# Cautin.net
KiCad netlist of a schematic drawn in EAGLE
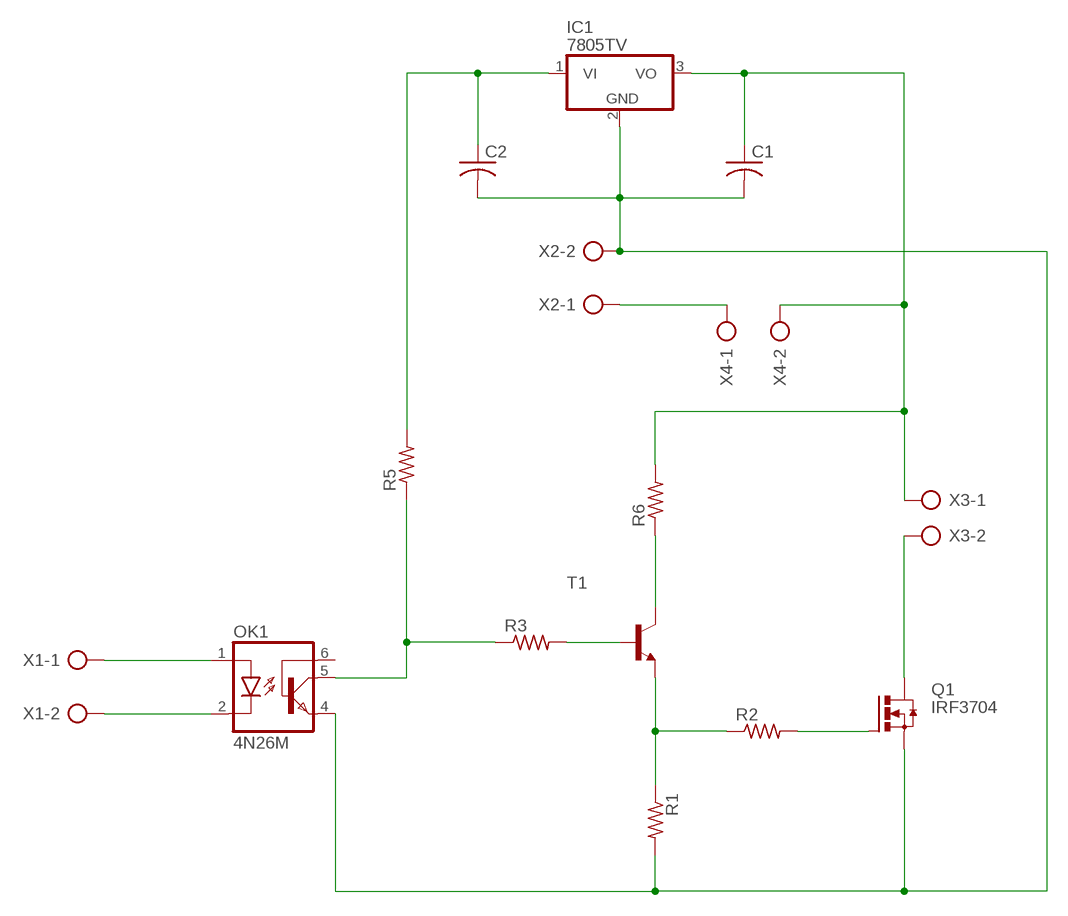
[diagram p0: schematic, sheet 1]

(export (version "E")
  (design (tool "Eeschema 10.0.6"))
  (components
    (comp (ref "C1")
      (value "C-US025-024X044")
      (footprint "eagle-import:C025-024X044")
      (libsource (lib "eagle-import") (part "C-US025-024X044"))
    )
    (comp (ref "C2")
      (value "C-US025-024X044")
      (footprint "eagle-import:C025-024X044")
      (libsource (lib "eagle-import") (part "C-US025-024X044"))
    )
    (comp (ref "IC1")
      (value "7805TV")
      (footprint "eagle-import:TO220V")
      (libsource (lib "eagle-import") (part "78TV05"))
    )
    (comp (ref "OK1")
      (value "4N26M")
      (footprint "eagle-import:DIL06")
      (fields (field (name "MPN") "4N26-M"))
      (libsource (lib "eagle-import") (part "4N?M26"))
    )
    (comp (ref "Q1")
      (value "IRF3704")
      (footprint "eagle-import:TO220AH")
      (libsource (lib "eagle-import") (part "IRF3704"))
    )
    (comp (ref "R1")
      (value "R-US_0207/12")
      (footprint "eagle-import:0207_12")
      (libsource (lib "eagle-import") (part "R-US_0207/12"))
    )
    (comp (ref "R2")
      (value "R-US_0207/12")
      (footprint "eagle-import:0207_12")
      (libsource (lib "eagle-import") (part "R-US_0207/12"))
    )
    (comp (ref "R3")
      (value "R-US_0207/12")
      (footprint "eagle-import:0207_12")
      (libsource (lib "eagle-import") (part "R-US_0207/12"))
    )
    (comp (ref "R5")
      (value "R-US_0207/12")
      (footprint "eagle-import:0207_12")
      (libsource (lib "eagle-import") (part "R-US_0207/12"))
    )
    (comp (ref "R6")
      (value "R-US_0207/15")
      (footprint "eagle-import:0207_15")
      (libsource (lib "eagle-import") (part "R-US_0207/15"))
    )
    (comp (ref "T1")
      (value "2N2222-NPN-TO92-EBC")
      (footprint "eagle-import:TO92-EBC")
      (libsource (lib "eagle-import") (part "-NPN-TO92-EBC2N2222"))
    )
    (comp (ref "X1")
      (value "AK500/2")
      (footprint "eagle-import:AK500_2")
      (libsource (lib "eagle-import") (part "AK500/2"))
    )
    (comp (ref "X2")
      (value "AK500/2")
      (footprint "eagle-import:AK500_2")
      (libsource (lib "eagle-import") (part "AK500/2"))
    )
    (comp (ref "X3")
      (value "AK500/2")
      (footprint "eagle-import:AK500_2")
      (libsource (lib "eagle-import") (part "AK500/2"))
    )
    (comp (ref "X4")
      (value "AK500/2")
      (footprint "eagle-import:AK500_2")
      (libsource (lib "eagle-import") (part "AK500/2"))
    )
  )
  (nets
    (net (code "1") (name "Net-(IC1-GND)") (class "Default")
      (node (ref "C1") (pin "2") (pinfunction "2_2") (pintype "passive"))
      (node (ref "C2") (pin "2") (pinfunction "2_2") (pintype "passive"))
      (node (ref "IC1") (pin "2") (pinfunction "GND_2") (pintype "passive"))
      (node (ref "OK1") (pin "4") (pinfunction "EMI_4") (pintype "passive"))
      (node (ref "Q1") (pin "E") (pinfunction "S_E") (pintype "passive"))
      (node (ref "R1") (pin "2") (pinfunction "2_2") (pintype "passive"))
      (node (ref "X2") (pin "2") (pinfunction "KL_2") (pintype "passive"))
    )
    (net (code "2") (name "Net-(IC1-VI)") (class "Default")
      (node (ref "C2") (pin "1") (pinfunction "1_1") (pintype "passive"))
      (node (ref "IC1") (pin "1") (pinfunction "VI_1") (pintype "input"))
      (node (ref "R5") (pin "2") (pinfunction "2_2") (pintype "passive"))
    )
    (net (code "3") (name "Net-(IC1-VO)") (class "Default")
      (node (ref "C1") (pin "1") (pinfunction "1_1") (pintype "passive"))
      (node (ref "IC1") (pin "3") (pinfunction "VO_3") (pintype "passive"))
      (node (ref "R6") (pin "2") (pinfunction "2_2") (pintype "passive"))
      (node (ref "X3") (pin "1") (pinfunction "KL_1") (pintype "passive"))
      (node (ref "X4") (pin "2") (pinfunction "KL_2") (pintype "passive"))
    )
    (net (code "4") (name "Net-(OK1-A)") (class "Default")
      (node (ref "OK1") (pin "1") (pinfunction "A_1") (pintype "passive"))
      (node (ref "X1") (pin "1") (pinfunction "KL_1") (pintype "passive"))
    )
    (net (code "5") (name "Net-(OK1-C)") (class "Default")
      (node (ref "OK1") (pin "2") (pinfunction "C_2") (pintype "passive"))
      (node (ref "X1") (pin "2") (pinfunction "KL_2") (pintype "passive"))
    )
    (net (code "6") (name "Net-(OK1-COL)") (class "Default")
      (node (ref "OK1") (pin "5") (pinfunction "COL_5") (pintype "passive"))
      (node (ref "R3") (pin "1") (pinfunction "1_1") (pintype "passive"))
      (node (ref "R5") (pin "1") (pinfunction "1_1") (pintype "passive"))
    )
    (net (code "7") (name "Net-(Q1-D)") (class "Default")
      (node (ref "Q1") (pin "C") (pinfunction "D_C") (pintype "passive"))
      (node (ref "X3") (pin "2") (pinfunction "KL_2") (pintype "passive"))
    )
    (net (code "8") (name "Net-(Q1-G)") (class "Default")
      (node (ref "Q1") (pin "B") (pinfunction "G_B") (pintype "passive"))
      (node (ref "R2") (pin "2") (pinfunction "2_2") (pintype "passive"))
    )
    (net (code "9") (name "Net-(R1-Pad1)") (class "Default")
      (node (ref "R1") (pin "1") (pinfunction "1_1") (pintype "passive"))
      (node (ref "R2") (pin "1") (pinfunction "1_1") (pintype "passive"))
      (node (ref "T1") (pin "E") (pinfunction "E_E") (pintype "passive"))
    )
    (net (code "10") (name "Net-(R3-Pad2)") (class "Default")
      (node (ref "R3") (pin "2") (pinfunction "2_2") (pintype "passive"))
      (node (ref "T1") (pin "B") (pinfunction "B_B") (pintype "passive"))
    )
    (net (code "11") (name "Net-(R6-Pad1)") (class "Default")
      (node (ref "R6") (pin "1") (pinfunction "1_1") (pintype "passive"))
      (node (ref "T1") (pin "C") (pinfunction "C_C") (pintype "passive"))
    )
    (net (code "12") (name "Net-(X2A-KL)") (class "Default")
      (node (ref "X2") (pin "1") (pinfunction "KL_1") (pintype "passive"))
      (node (ref "X4") (pin "1") (pinfunction "KL_1") (pintype "passive"))
    )
    (net (code "13") (name "unconnected-(OK1-BAS-Pad6)") (class "Default")
      (node (ref "OK1") (pin "6") (pinfunction "BAS_6") (pintype "passive"))
    )
  )
)
